# I2C_switch.net
KiCad netlist of a schematic drawn in Altium Designer
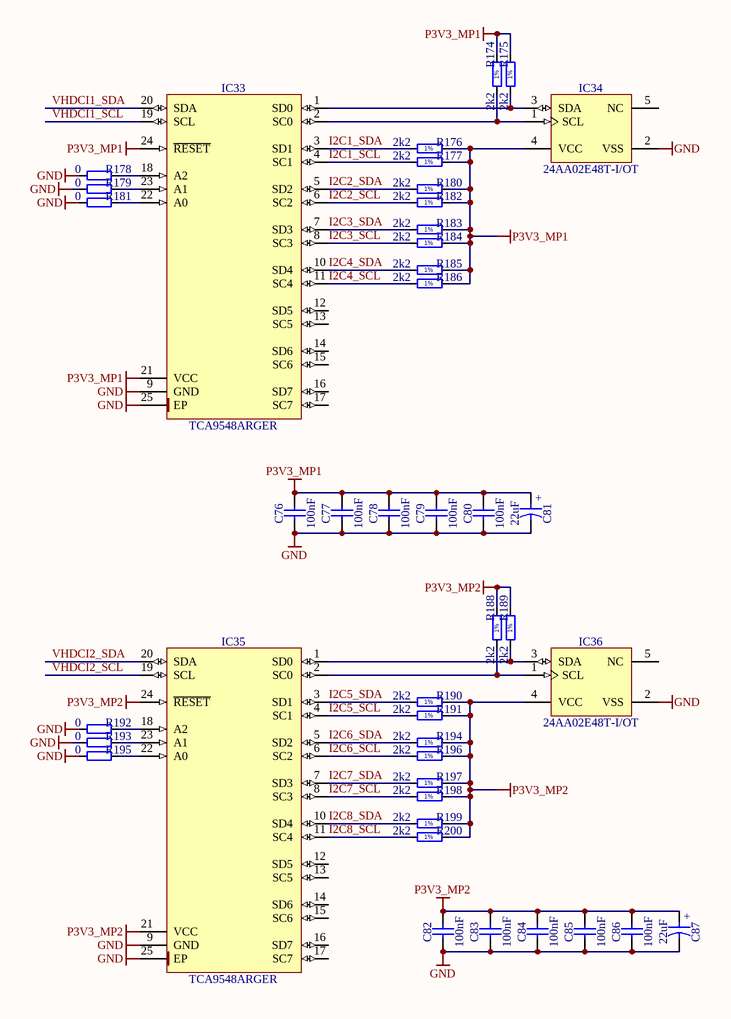
[diagram p0: I2C_switch.SchDoc]

(export (version "E")
  (design (tool "Eeschema 10.0.6"))
  (components
    (comp (ref "C76")
      (value "100nF")
      (footprint "CAPC1005X55N")
      (description "Non-polarised capacitor")
      (fields
        (field (name "PART NUMBER") "CC0402_100NF_16V_10%_X5R")
        (field (name "VOLTAGE") "16V")
        (field (name "AUTHOR") "CERN DEM JLC")
      )
      (libsource (lib "Capacitors") (part "Capacitor - non polarized"))
    )
    (comp (ref "C77")
      (value "100nF")
      (footprint "CAPC1005X55N")
      (description "Non-polarised capacitor")
      (fields
        (field (name "PART NUMBER") "CC0402_100NF_16V_10%_X5R")
        (field (name "VOLTAGE") "16V")
        (field (name "AUTHOR") "CERN DEM JLC")
      )
      (libsource (lib "Capacitors") (part "Capacitor - non polarized"))
    )
    (comp (ref "C78")
      (value "100nF")
      (footprint "CAPC1005X55N")
      (description "Non-polarised capacitor")
      (fields
        (field (name "PART NUMBER") "CC0402_100NF_16V_10%_X5R")
        (field (name "VOLTAGE") "16V")
        (field (name "AUTHOR") "CERN DEM JLC")
      )
      (libsource (lib "Capacitors") (part "Capacitor - non polarized"))
    )
    (comp (ref "C79")
      (value "100nF")
      (footprint "CAPC1005X55N")
      (description "Non-polarised capacitor")
      (fields
        (field (name "PART NUMBER") "CC0402_100NF_16V_10%_X5R")
        (field (name "VOLTAGE") "16V")
        (field (name "AUTHOR") "CERN DEM JLC")
      )
      (libsource (lib "Capacitors") (part "Capacitor - non polarized"))
    )
    (comp (ref "C80")
      (value "100nF")
      (footprint "CAPC1005X55N")
      (description "Non-polarised capacitor")
      (fields
        (field (name "PART NUMBER") "CC0402_100NF_16V_10%_X5R")
        (field (name "VOLTAGE") "16V")
        (field (name "AUTHOR") "CERN DEM JLC")
      )
      (libsource (lib "Capacitors") (part "Capacitor - non polarized"))
    )
    (comp (ref "C81")
      (value "22uF")
      (footprint "CAPAE530X540N")
      (description "Polarised capacitor")
      (fields
        (field (name "PART NUMBER") "CAE530-540_22UF_16V_20%")
        (field (name "VOLTAGE") "16V")
        (field (name "AUTHOR") "CERN DEM JLC")
      )
      (libsource (lib "Capacitors") (part "Capacitor - polarized"))
    )
    (comp (ref "C82")
      (value "100nF")
      (footprint "CAPC1005X55N")
      (description "Non-polarised capacitor")
      (fields
        (field (name "PART NUMBER") "CC0402_100NF_16V_10%_X5R")
        (field (name "VOLTAGE") "16V")
        (field (name "AUTHOR") "CERN DEM JLC")
      )
      (libsource (lib "Capacitors") (part "Capacitor - non polarized"))
    )
    (comp (ref "C83")
      (value "100nF")
      (footprint "CAPC1005X55N")
      (description "Non-polarised capacitor")
      (fields
        (field (name "PART NUMBER") "CC0402_100NF_16V_10%_X5R")
        (field (name "VOLTAGE") "16V")
        (field (name "AUTHOR") "CERN DEM JLC")
      )
      (libsource (lib "Capacitors") (part "Capacitor - non polarized"))
    )
    (comp (ref "C84")
      (value "100nF")
      (footprint "CAPC1005X55N")
      (description "Non-polarised capacitor")
      (fields
        (field (name "PART NUMBER") "CC0402_100NF_16V_10%_X5R")
        (field (name "VOLTAGE") "16V")
        (field (name "AUTHOR") "CERN DEM JLC")
      )
      (libsource (lib "Capacitors") (part "Capacitor - non polarized"))
    )
    (comp (ref "C85")
      (value "100nF")
      (footprint "CAPC1005X55N")
      (description "Non-polarised capacitor")
      (fields
        (field (name "PART NUMBER") "CC0402_100NF_16V_10%_X5R")
        (field (name "VOLTAGE") "16V")
        (field (name "AUTHOR") "CERN DEM JLC")
      )
      (libsource (lib "Capacitors") (part "Capacitor - non polarized"))
    )
    (comp (ref "C86")
      (value "100nF")
      (footprint "CAPC1005X55N")
      (description "Non-polarised capacitor")
      (fields
        (field (name "PART NUMBER") "CC0402_100NF_16V_10%_X5R")
        (field (name "VOLTAGE") "16V")
        (field (name "AUTHOR") "CERN DEM JLC")
      )
      (libsource (lib "Capacitors") (part "Capacitor - non polarized"))
    )
    (comp (ref "C87")
      (value "22uF")
      (footprint "CAPAE530X540N")
      (description "Polarised capacitor")
      (fields
        (field (name "PART NUMBER") "CAE530-540_22UF_16V_20%")
        (field (name "VOLTAGE") "16V")
        (field (name "AUTHOR") "CERN DEM JLC")
      )
      (libsource (lib "Capacitors") (part "Capacitor - polarized"))
    )
    (comp (ref "IC33")
      (value "TCA9548ARGER")
      (footprint "QFN50P400X400X100-25N-S220")
      (description "Low Voltage 8-Channel I2C Switch With Reset")
      (fields (field (name "MANUFACTURER") "TEXAS INSTRUMENTS") (field (name "AUTHOR") "CERN DEM JLC"))
      (libsource (lib "ICs And Semiconductors") (part "TCA9548ARGER"))
    )
    (comp (ref "IC34")
      (value "24AA02E48T-I/OT")
      (footprint "SOT95P280X145-5N")
      (description "1.7V-5.5V, 2K I2C Serial EEPROM With EUI-48 Node Identity")
      (fields (field (name "MANUFACTURER") "MICROCHIP TECHNOLOGY") (field (name "AUTHOR") "CERN DEM MR"))
      (libsource (lib "ICs And Semiconductors") (part "24AA02E48T-I/OT"))
    )
    (comp (ref "IC35")
      (value "TCA9548ARGER")
      (footprint "QFN50P400X400X100-25N-S220")
      (description "Low Voltage 8-Channel I2C Switch With Reset")
      (fields (field (name "MANUFACTURER") "TEXAS INSTRUMENTS") (field (name "AUTHOR") "CERN DEM JLC"))
      (libsource (lib "ICs And Semiconductors") (part "TCA9548ARGER"))
    )
    (comp (ref "IC36")
      (value "24AA02E48T-I/OT")
      (footprint "SOT95P280X145-5N")
      (description "1.7V-5.5V, 2K I2C Serial EEPROM With EUI-48 Node Identity")
      (fields (field (name "MANUFACTURER") "MICROCHIP TECHNOLOGY") (field (name "AUTHOR") "CERN DEM MR"))
      (libsource (lib "ICs And Semiconductors") (part "24AA02E48T-I/OT"))
    )
    (comp (ref "R174")
      (value "2k2")
      (footprint "RESC1005X40N")
      (description "Resistor - 1%")
      (fields
        (field (name "PART NUMBER") "R0402_2K2_1%_0.0625W_100PPM")
        (field (name "POWER") "0.0625W")
        (field (name "AUTHOR") "CERN DEM JLC")
      )
      (libsource (lib "Resistors") (part "Resistor - 1%"))
    )
    (comp (ref "R175")
      (value "2k2")
      (footprint "RESC1005X40N")
      (description "Resistor - 1%")
      (fields
        (field (name "PART NUMBER") "R0402_2K2_1%_0.0625W_100PPM")
        (field (name "POWER") "0.0625W")
        (field (name "AUTHOR") "CERN DEM JLC")
      )
      (libsource (lib "Resistors") (part "Resistor - 1%"))
    )
    (comp (ref "R176")
      (value "2k2")
      (footprint "RESC1005X40N")
      (description "Resistor - 1%")
      (fields
        (field (name "PART NUMBER") "R0402_2K2_1%_0.0625W_100PPM")
        (field (name "POWER") "0.0625W")
        (field (name "AUTHOR") "CERN DEM JLC")
      )
      (libsource (lib "Resistors") (part "Resistor - 1%"))
    )
    (comp (ref "R177")
      (value "2k2")
      (footprint "RESC1005X40N")
      (description "Resistor - 1%")
      (fields
        (field (name "PART NUMBER") "R0402_2K2_1%_0.0625W_100PPM")
        (field (name "POWER") "0.0625W")
        (field (name "AUTHOR") "CERN DEM JLC")
      )
      (libsource (lib "Resistors") (part "Resistor - 1%"))
    )
    (comp (ref "R178")
      (value "0")
      (footprint "RESC1005X40N")
      (description "Resistor")
      (fields
        (field (name "PART NUMBER") "R0402_0R_JUMPER")
        (field (name "MANUFACTURER") "GENERIC")
        (field (name "AUTHOR") "CERN DEM JLC")
      )
      (libsource (lib "Resistors") (part "Resistor"))
    )
    (comp (ref "R179")
      (value "0")
      (footprint "RESC1005X40N")
      (description "Resistor")
      (fields
        (field (name "PART NUMBER") "R0402_0R_JUMPER")
        (field (name "MANUFACTURER") "GENERIC")
        (field (name "AUTHOR") "CERN DEM JLC")
      )
      (libsource (lib "Resistors") (part "Resistor"))
    )
    (comp (ref "R180")
      (value "2k2")
      (footprint "RESC1005X40N")
      (description "Resistor - 1%")
      (fields
        (field (name "PART NUMBER") "R0402_2K2_1%_0.0625W_100PPM")
        (field (name "POWER") "0.0625W")
        (field (name "AUTHOR") "CERN DEM JLC")
      )
      (libsource (lib "Resistors") (part "Resistor - 1%"))
    )
    (comp (ref "R181")
      (value "0")
      (footprint "RESC1005X40N")
      (description "Resistor")
      (fields
        (field (name "PART NUMBER") "R0402_0R_JUMPER")
        (field (name "MANUFACTURER") "GENERIC")
        (field (name "AUTHOR") "CERN DEM JLC")
      )
      (libsource (lib "Resistors") (part "Resistor"))
    )
    (comp (ref "R182")
      (value "2k2")
      (footprint "RESC1005X40N")
      (description "Resistor - 1%")
      (fields
        (field (name "PART NUMBER") "R0402_2K2_1%_0.0625W_100PPM")
        (field (name "POWER") "0.0625W")
        (field (name "AUTHOR") "CERN DEM JLC")
      )
      (libsource (lib "Resistors") (part "Resistor - 1%"))
    )
    (comp (ref "R183")
      (value "2k2")
      (footprint "RESC1005X40N")
      (description "Resistor - 1%")
      (fields
        (field (name "PART NUMBER") "R0402_2K2_1%_0.0625W_100PPM")
        (field (name "POWER") "0.0625W")
        (field (name "AUTHOR") "CERN DEM JLC")
      )
      (libsource (lib "Resistors") (part "Resistor - 1%"))
    )
    (comp (ref "R184")
      (value "2k2")
      (footprint "RESC1005X40N")
      (description "Resistor - 1%")
      (fields
        (field (name "PART NUMBER") "R0402_2K2_1%_0.0625W_100PPM")
        (field (name "POWER") "0.0625W")
        (field (name "AUTHOR") "CERN DEM JLC")
      )
      (libsource (lib "Resistors") (part "Resistor - 1%"))
    )
    (comp (ref "R185")
      (value "2k2")
      (footprint "RESC1005X40N")
      (description "Resistor - 1%")
      (fields
        (field (name "PART NUMBER") "R0402_2K2_1%_0.0625W_100PPM")
        (field (name "POWER") "0.0625W")
        (field (name "AUTHOR") "CERN DEM JLC")
      )
      (libsource (lib "Resistors") (part "Resistor - 1%"))
    )
    (comp (ref "R186")
      (value "2k2")
      (footprint "RESC1005X40N")
      (description "Resistor - 1%")
      (fields
        (field (name "PART NUMBER") "R0402_2K2_1%_0.0625W_100PPM")
        (field (name "POWER") "0.0625W")
        (field (name "AUTHOR") "CERN DEM JLC")
      )
      (libsource (lib "Resistors") (part "Resistor - 1%"))
    )
    (comp (ref "R188")
      (value "2k2")
      (footprint "RESC1005X40N")
      (description "Resistor - 1%")
      (fields
        (field (name "PART NUMBER") "R0402_2K2_1%_0.0625W_100PPM")
        (field (name "POWER") "0.0625W")
        (field (name "AUTHOR") "CERN DEM JLC")
      )
      (libsource (lib "Resistors") (part "Resistor - 1%"))
    )
    (comp (ref "R189")
      (value "2k2")
      (footprint "RESC1005X40N")
      (description "Resistor - 1%")
      (fields
        (field (name "PART NUMBER") "R0402_2K2_1%_0.0625W_100PPM")
        (field (name "POWER") "0.0625W")
        (field (name "AUTHOR") "CERN DEM JLC")
      )
      (libsource (lib "Resistors") (part "Resistor - 1%"))
    )
    (comp (ref "R190")
      (value "2k2")
      (footprint "RESC1005X40N")
      (description "Resistor - 1%")
      (fields
        (field (name "PART NUMBER") "R0402_2K2_1%_0.0625W_100PPM")
        (field (name "POWER") "0.0625W")
        (field (name "AUTHOR") "CERN DEM JLC")
      )
      (libsource (lib "Resistors") (part "Resistor - 1%"))
    )
    (comp (ref "R191")
      (value "2k2")
      (footprint "RESC1005X40N")
      (description "Resistor - 1%")
      (fields
        (field (name "PART NUMBER") "R0402_2K2_1%_0.0625W_100PPM")
        (field (name "POWER") "0.0625W")
        (field (name "AUTHOR") "CERN DEM JLC")
      )
      (libsource (lib "Resistors") (part "Resistor - 1%"))
    )
    (comp (ref "R192")
      (value "0")
      (footprint "RESC1005X40N")
      (description "Resistor")
      (fields
        (field (name "PART NUMBER") "R0402_0R_JUMPER")
        (field (name "MANUFACTURER") "GENERIC")
        (field (name "AUTHOR") "CERN DEM JLC")
      )
      (libsource (lib "Resistors") (part "Resistor"))
    )
    (comp (ref "R193")
      (value "0")
      (footprint "RESC1005X40N")
      (description "Resistor")
      (fields
        (field (name "PART NUMBER") "R0402_0R_JUMPER")
        (field (name "MANUFACTURER") "GENERIC")
        (field (name "AUTHOR") "CERN DEM JLC")
      )
      (libsource (lib "Resistors") (part "Resistor"))
    )
    (comp (ref "R194")
      (value "2k2")
      (footprint "RESC1005X40N")
      (description "Resistor - 1%")
      (fields
        (field (name "PART NUMBER") "R0402_2K2_1%_0.0625W_100PPM")
        (field (name "POWER") "0.0625W")
        (field (name "AUTHOR") "CERN DEM JLC")
      )
      (libsource (lib "Resistors") (part "Resistor - 1%"))
    )
    (comp (ref "R195")
      (value "0")
      (footprint "RESC1005X40N")
      (description "Resistor")
      (fields
        (field (name "PART NUMBER") "R0402_0R_JUMPER")
        (field (name "MANUFACTURER") "GENERIC")
        (field (name "AUTHOR") "CERN DEM JLC")
      )
      (libsource (lib "Resistors") (part "Resistor"))
    )
    (comp (ref "R196")
      (value "2k2")
      (footprint "RESC1005X40N")
      (description "Resistor - 1%")
      (fields
        (field (name "PART NUMBER") "R0402_2K2_1%_0.0625W_100PPM")
        (field (name "POWER") "0.0625W")
        (field (name "AUTHOR") "CERN DEM JLC")
      )
      (libsource (lib "Resistors") (part "Resistor - 1%"))
    )
    (comp (ref "R197")
      (value "2k2")
      (footprint "RESC1005X40N")
      (description "Resistor - 1%")
      (fields
        (field (name "PART NUMBER") "R0402_2K2_1%_0.0625W_100PPM")
        (field (name "POWER") "0.0625W")
        (field (name "AUTHOR") "CERN DEM JLC")
      )
      (libsource (lib "Resistors") (part "Resistor - 1%"))
    )
    (comp (ref "R198")
      (value "2k2")
      (footprint "RESC1005X40N")
      (description "Resistor - 1%")
      (fields
        (field (name "PART NUMBER") "R0402_2K2_1%_0.0625W_100PPM")
        (field (name "POWER") "0.0625W")
        (field (name "AUTHOR") "CERN DEM JLC")
      )
      (libsource (lib "Resistors") (part "Resistor - 1%"))
    )
    (comp (ref "R199")
      (value "2k2")
      (footprint "RESC1005X40N")
      (description "Resistor - 1%")
      (fields
        (field (name "PART NUMBER") "R0402_2K2_1%_0.0625W_100PPM")
        (field (name "POWER") "0.0625W")
        (field (name "AUTHOR") "CERN DEM JLC")
      )
      (libsource (lib "Resistors") (part "Resistor - 1%"))
    )
    (comp (ref "R200")
      (value "2k2")
      (footprint "RESC1005X40N")
      (description "Resistor - 1%")
      (fields
        (field (name "PART NUMBER") "R0402_2K2_1%_0.0625W_100PPM")
        (field (name "POWER") "0.0625W")
        (field (name "AUTHOR") "CERN DEM JLC")
      )
      (libsource (lib "Resistors") (part "Resistor - 1%"))
    )
  )
  (nets
    (net (code "1") (name "/I2C1_SCL") (class "Default")
      (node (ref "IC33") (pin "4") (pinfunction "SC1_4") (pintype "bidirectional"))
      (node (ref "R177") (pin "1") (pinfunction "1_1") (pintype "passive"))
    )
    (net (code "2") (name "/I2C1_SDA") (class "Default")
      (node (ref "IC33") (pin "3") (pinfunction "SD1_3") (pintype "bidirectional"))
      (node (ref "R176") (pin "1") (pinfunction "1_1") (pintype "passive"))
    )
    (net (code "3") (name "/I2C2_SCL") (class "Default")
      (node (ref "IC33") (pin "6") (pinfunction "SC2_6") (pintype "bidirectional"))
      (node (ref "R182") (pin "1") (pinfunction "1_1") (pintype "passive"))
    )
    (net (code "4") (name "/I2C2_SDA") (class "Default")
      (node (ref "IC33") (pin "5") (pinfunction "SD2_5") (pintype "bidirectional"))
      (node (ref "R180") (pin "1") (pinfunction "1_1") (pintype "passive"))
    )
    (net (code "5") (name "/I2C3_SCL") (class "Default")
      (node (ref "IC33") (pin "8") (pinfunction "SC3_8") (pintype "bidirectional"))
      (node (ref "R184") (pin "1") (pinfunction "1_1") (pintype "passive"))
    )
    (net (code "6") (name "/I2C3_SDA") (class "Default")
      (node (ref "IC33") (pin "7") (pinfunction "SD3_7") (pintype "bidirectional"))
      (node (ref "R183") (pin "1") (pinfunction "1_1") (pintype "passive"))
    )
    (net (code "7") (name "/I2C4_SCL") (class "Default")
      (node (ref "IC33") (pin "11") (pinfunction "SC4_11") (pintype "bidirectional"))
      (node (ref "R186") (pin "1") (pinfunction "1_1") (pintype "passive"))
    )
    (net (code "8") (name "/I2C4_SDA") (class "Default")
      (node (ref "IC33") (pin "10") (pinfunction "SD4_10") (pintype "bidirectional"))
      (node (ref "R185") (pin "1") (pinfunction "1_1") (pintype "passive"))
    )
    (net (code "9") (name "/I2C5_SCL") (class "Default")
      (node (ref "IC35") (pin "4") (pinfunction "SC1_4") (pintype "bidirectional"))
      (node (ref "R191") (pin "1") (pinfunction "1_1") (pintype "passive"))
    )
    (net (code "10") (name "/I2C5_SDA") (class "Default")
      (node (ref "IC35") (pin "3") (pinfunction "SD1_3") (pintype "bidirectional"))
      (node (ref "R190") (pin "1") (pinfunction "1_1") (pintype "passive"))
    )
    (net (code "11") (name "/I2C6_SCL") (class "Default")
      (node (ref "IC35") (pin "6") (pinfunction "SC2_6") (pintype "bidirectional"))
      (node (ref "R196") (pin "1") (pinfunction "1_1") (pintype "passive"))
    )
    (net (code "12") (name "/I2C6_SDA") (class "Default")
      (node (ref "IC35") (pin "5") (pinfunction "SD2_5") (pintype "bidirectional"))
      (node (ref "R194") (pin "1") (pinfunction "1_1") (pintype "passive"))
    )
    (net (code "13") (name "/I2C7_SCL") (class "Default")
      (node (ref "IC35") (pin "8") (pinfunction "SC3_8") (pintype "bidirectional"))
      (node (ref "R198") (pin "1") (pinfunction "1_1") (pintype "passive"))
    )
    (net (code "14") (name "/I2C7_SDA") (class "Default")
      (node (ref "IC35") (pin "7") (pinfunction "SD3_7") (pintype "bidirectional"))
      (node (ref "R197") (pin "1") (pinfunction "1_1") (pintype "passive"))
    )
    (net (code "15") (name "/I2C8_SCL") (class "Default")
      (node (ref "IC35") (pin "11") (pinfunction "SC4_11") (pintype "bidirectional"))
      (node (ref "R200") (pin "1") (pinfunction "1_1") (pintype "passive"))
    )
    (net (code "16") (name "/I2C8_SDA") (class "Default")
      (node (ref "IC35") (pin "10") (pinfunction "SD4_10") (pintype "bidirectional"))
      (node (ref "R199") (pin "1") (pinfunction "1_1") (pintype "passive"))
    )
    (net (code "17") (name "/VHDCI1_SCL") (class "Default")
      (node (ref "IC33") (pin "19") (pinfunction "SCL_19") (pintype "bidirectional"))
    )
    (net (code "18") (name "/VHDCI1_SDA") (class "Default")
      (node (ref "IC33") (pin "20") (pinfunction "SDA_20") (pintype "bidirectional"))
    )
    (net (code "19") (name "/VHDCI2_SCL") (class "Default")
      (node (ref "IC35") (pin "19") (pinfunction "SCL_19") (pintype "bidirectional"))
    )
    (net (code "20") (name "/VHDCI2_SDA") (class "Default")
      (node (ref "IC35") (pin "20") (pinfunction "SDA_20") (pintype "bidirectional"))
    )
    (net (code "21") (name "GND") (class "Default")
      (node (ref "C76") (pin "1") (pinfunction "1_1") (pintype "passive"))
      (node (ref "C77") (pin "1") (pinfunction "1_1") (pintype "passive"))
      (node (ref "C78") (pin "1") (pinfunction "1_1") (pintype "passive"))
      (node (ref "C79") (pin "1") (pinfunction "1_1") (pintype "passive"))
      (node (ref "C80") (pin "1") (pinfunction "1_1") (pintype "passive"))
      (node (ref "C81") (pin "2") (pinfunction "2_2") (pintype "passive"))
      (node (ref "C82") (pin "1") (pinfunction "1_1") (pintype "passive"))
      (node (ref "C83") (pin "1") (pinfunction "1_1") (pintype "passive"))
      (node (ref "C84") (pin "1") (pinfunction "1_1") (pintype "passive"))
      (node (ref "C85") (pin "1") (pinfunction "1_1") (pintype "passive"))
      (node (ref "C86") (pin "1") (pinfunction "1_1") (pintype "passive"))
      (node (ref "C87") (pin "2") (pinfunction "2_2") (pintype "passive"))
      (node (ref "IC33") (pin "25") (pinfunction "EP_25") (pintype "power_in"))
      (node (ref "IC33") (pin "9") (pinfunction "GND_9") (pintype "power_in"))
      (node (ref "IC34") (pin "2") (pinfunction "VSS_2") (pintype "power_in"))
      (node (ref "IC35") (pin "25") (pinfunction "EP_25") (pintype "power_in"))
      (node (ref "IC35") (pin "9") (pinfunction "GND_9") (pintype "power_in"))
      (node (ref "IC36") (pin "2") (pinfunction "VSS_2") (pintype "power_in"))
      (node (ref "R178") (pin "1") (pinfunction "1_1") (pintype "passive"))
      (node (ref "R179") (pin "1") (pinfunction "1_1") (pintype "passive"))
      (node (ref "R181") (pin "1") (pinfunction "1_1") (pintype "passive"))
      (node (ref "R192") (pin "1") (pinfunction "1_1") (pintype "passive"))
      (node (ref "R193") (pin "1") (pinfunction "1_1") (pintype "passive"))
      (node (ref "R195") (pin "1") (pinfunction "1_1") (pintype "passive"))
    )
    (net (code "22") (name "Net-(IC33-A0)") (class "Default")
      (node (ref "IC33") (pin "22") (pinfunction "A0_22") (pintype "input"))
      (node (ref "R181") (pin "2") (pinfunction "2_2") (pintype "passive"))
    )
    (net (code "23") (name "Net-(IC33-A1)") (class "Default")
      (node (ref "IC33") (pin "23") (pinfunction "A1_23") (pintype "input"))
      (node (ref "R179") (pin "2") (pinfunction "2_2") (pintype "passive"))
    )
    (net (code "24") (name "Net-(IC33-A2)") (class "Default")
      (node (ref "IC33") (pin "18") (pinfunction "A2_18") (pintype "input"))
      (node (ref "R178") (pin "2") (pinfunction "2_2") (pintype "passive"))
    )
    (net (code "25") (name "Net-(IC33-SC0)") (class "Default")
      (node (ref "IC33") (pin "2") (pinfunction "SC0_2") (pintype "bidirectional"))
      (node (ref "IC34") (pin "1") (pinfunction "SCL_1") (pintype "input"))
      (node (ref "R174") (pin "1") (pinfunction "1_1") (pintype "passive"))
    )
    (net (code "26") (name "Net-(IC33-SD0)") (class "Default")
      (node (ref "IC33") (pin "1") (pinfunction "SD0_1") (pintype "bidirectional"))
      (node (ref "IC34") (pin "3") (pinfunction "SDA_3") (pintype "bidirectional"))
      (node (ref "R175") (pin "1") (pinfunction "1_1") (pintype "passive"))
    )
    (net (code "27") (name "Net-(IC35-A0)") (class "Default")
      (node (ref "IC35") (pin "22") (pinfunction "A0_22") (pintype "input"))
      (node (ref "R195") (pin "2") (pinfunction "2_2") (pintype "passive"))
    )
    (net (code "28") (name "Net-(IC35-A1)") (class "Default")
      (node (ref "IC35") (pin "23") (pinfunction "A1_23") (pintype "input"))
      (node (ref "R193") (pin "2") (pinfunction "2_2") (pintype "passive"))
    )
    (net (code "29") (name "Net-(IC35-A2)") (class "Default")
      (node (ref "IC35") (pin "18") (pinfunction "A2_18") (pintype "input"))
      (node (ref "R192") (pin "2") (pinfunction "2_2") (pintype "passive"))
    )
    (net (code "30") (name "Net-(IC35-SC0)") (class "Default")
      (node (ref "IC35") (pin "2") (pinfunction "SC0_2") (pintype "bidirectional"))
      (node (ref "IC36") (pin "1") (pinfunction "SCL_1") (pintype "input"))
      (node (ref "R188") (pin "1") (pinfunction "1_1") (pintype "passive"))
    )
    (net (code "31") (name "Net-(IC35-SD0)") (class "Default")
      (node (ref "IC35") (pin "1") (pinfunction "SD0_1") (pintype "bidirectional"))
      (node (ref "IC36") (pin "3") (pinfunction "SDA_3") (pintype "bidirectional"))
      (node (ref "R189") (pin "1") (pinfunction "1_1") (pintype "passive"))
    )
    (net (code "32") (name "P3V3_MP1") (class "Default")
      (node (ref "C76") (pin "2") (pinfunction "2_2") (pintype "passive"))
      (node (ref "C77") (pin "2") (pinfunction "2_2") (pintype "passive"))
      (node (ref "C78") (pin "2") (pinfunction "2_2") (pintype "passive"))
      (node (ref "C79") (pin "2") (pinfunction "2_2") (pintype "passive"))
      (node (ref "C80") (pin "2") (pinfunction "2_2") (pintype "passive"))
      (node (ref "C81") (pin "1") (pinfunction "1_1") (pintype "passive"))
      (node (ref "IC33") (pin "21") (pinfunction "VCC_21") (pintype "power_in"))
      (node (ref "IC33") (pin "24") (pinfunction "~{RESET}_24") (pintype "input"))
      (node (ref "IC34") (pin "4") (pinfunction "VCC_4") (pintype "power_in"))
      (node (ref "R174") (pin "2") (pinfunction "2_2") (pintype "passive"))
      (node (ref "R175") (pin "2") (pinfunction "2_2") (pintype "passive"))
      (node (ref "R176") (pin "2") (pinfunction "2_2") (pintype "passive"))
      (node (ref "R177") (pin "2") (pinfunction "2_2") (pintype "passive"))
      (node (ref "R180") (pin "2") (pinfunction "2_2") (pintype "passive"))
      (node (ref "R182") (pin "2") (pinfunction "2_2") (pintype "passive"))
      (node (ref "R183") (pin "2") (pinfunction "2_2") (pintype "passive"))
      (node (ref "R184") (pin "2") (pinfunction "2_2") (pintype "passive"))
      (node (ref "R185") (pin "2") (pinfunction "2_2") (pintype "passive"))
      (node (ref "R186") (pin "2") (pinfunction "2_2") (pintype "passive"))
    )
    (net (code "33") (name "P3V3_MP2") (class "Default")
      (node (ref "C82") (pin "2") (pinfunction "2_2") (pintype "passive"))
      (node (ref "C83") (pin "2") (pinfunction "2_2") (pintype "passive"))
      (node (ref "C84") (pin "2") (pinfunction "2_2") (pintype "passive"))
      (node (ref "C85") (pin "2") (pinfunction "2_2") (pintype "passive"))
      (node (ref "C86") (pin "2") (pinfunction "2_2") (pintype "passive"))
      (node (ref "C87") (pin "1") (pinfunction "1_1") (pintype "passive"))
      (node (ref "IC35") (pin "21") (pinfunction "VCC_21") (pintype "power_in"))
      (node (ref "IC35") (pin "24") (pinfunction "~{RESET}_24") (pintype "input"))
      (node (ref "IC36") (pin "4") (pinfunction "VCC_4") (pintype "power_in"))
      (node (ref "R188") (pin "2") (pinfunction "2_2") (pintype "passive"))
      (node (ref "R189") (pin "2") (pinfunction "2_2") (pintype "passive"))
      (node (ref "R190") (pin "2") (pinfunction "2_2") (pintype "passive"))
      (node (ref "R191") (pin "2") (pinfunction "2_2") (pintype "passive"))
      (node (ref "R194") (pin "2") (pinfunction "2_2") (pintype "passive"))
      (node (ref "R196") (pin "2") (pinfunction "2_2") (pintype "passive"))
      (node (ref "R197") (pin "2") (pinfunction "2_2") (pintype "passive"))
      (node (ref "R198") (pin "2") (pinfunction "2_2") (pintype "passive"))
      (node (ref "R199") (pin "2") (pinfunction "2_2") (pintype "passive"))
      (node (ref "R200") (pin "2") (pinfunction "2_2") (pintype "passive"))
    )
    (net (code "34") (name "unconnected-(IC33-SC5-Pad13)") (class "Default")
      (node (ref "IC33") (pin "13") (pinfunction "SC5_13") (pintype "bidirectional"))
    )
    (net (code "35") (name "unconnected-(IC33-SC6-Pad15)") (class "Default")
      (node (ref "IC33") (pin "15") (pinfunction "SC6_15") (pintype "bidirectional"))
    )
    (net (code "36") (name "unconnected-(IC33-SC7-Pad17)") (class "Default")
      (node (ref "IC33") (pin "17") (pinfunction "SC7_17") (pintype "bidirectional"))
    )
    (net (code "37") (name "unconnected-(IC33-SD5-Pad12)") (class "Default")
      (node (ref "IC33") (pin "12") (pinfunction "SD5_12") (pintype "bidirectional"))
    )
    (net (code "38") (name "unconnected-(IC33-SD6-Pad14)") (class "Default")
      (node (ref "IC33") (pin "14") (pinfunction "SD6_14") (pintype "bidirectional"))
    )
    (net (code "39") (name "unconnected-(IC33-SD7-Pad16)") (class "Default")
      (node (ref "IC33") (pin "16") (pinfunction "SD7_16") (pintype "bidirectional"))
    )
    (net (code "40") (name "unconnected-(IC34-NC-Pad5)") (class "Default")
      (node (ref "IC34") (pin "5") (pinfunction "NC_5") (pintype "passive"))
    )
    (net (code "41") (name "unconnected-(IC35-SC5-Pad13)") (class "Default")
      (node (ref "IC35") (pin "13") (pinfunction "SC5_13") (pintype "bidirectional"))
    )
    (net (code "42") (name "unconnected-(IC35-SC6-Pad15)") (class "Default")
      (node (ref "IC35") (pin "15") (pinfunction "SC6_15") (pintype "bidirectional"))
    )
    (net (code "43") (name "unconnected-(IC35-SC7-Pad17)") (class "Default")
      (node (ref "IC35") (pin "17") (pinfunction "SC7_17") (pintype "bidirectional"))
    )
    (net (code "44") (name "unconnected-(IC35-SD5-Pad12)") (class "Default")
      (node (ref "IC35") (pin "12") (pinfunction "SD5_12") (pintype "bidirectional"))
    )
    (net (code "45") (name "unconnected-(IC35-SD6-Pad14)") (class "Default")
      (node (ref "IC35") (pin "14") (pinfunction "SD6_14") (pintype "bidirectional"))
    )
    (net (code "46") (name "unconnected-(IC35-SD7-Pad16)") (class "Default")
      (node (ref "IC35") (pin "16") (pinfunction "SD7_16") (pintype "bidirectional"))
    )
    (net (code "47") (name "unconnected-(IC36-NC-Pad5)") (class "Default")
      (node (ref "IC36") (pin "5") (pinfunction "NC_5") (pintype "passive"))
    )
  )
)
